# FG_with_AD9833.net
KiCad netlist of a schematic drawn in EAGLE
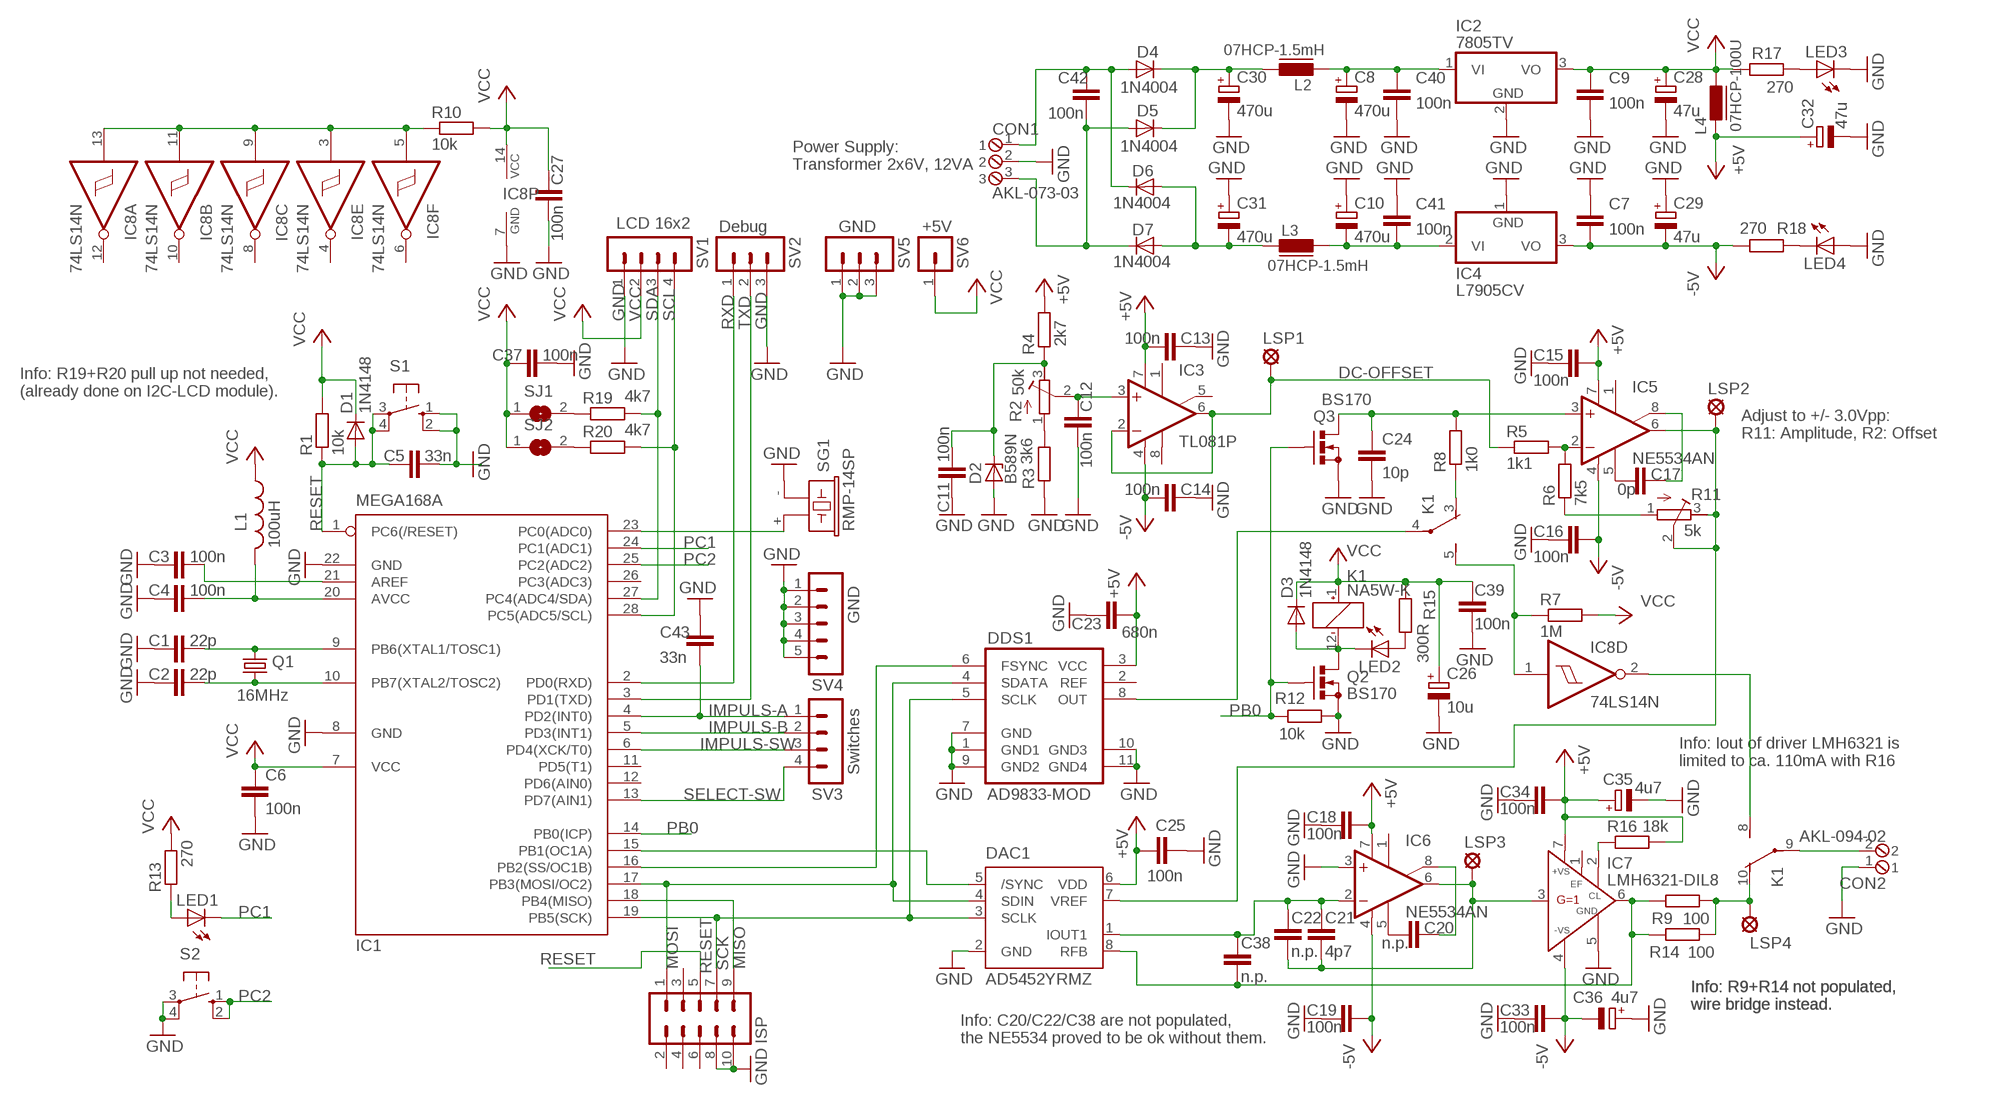
[diagram p0: schematic, sheet 1]

(export (version "E")
  (design (tool "Eeschema 10.0.6"))
  (components
    (comp (ref "C1")
      (value "22p")
      (footprint "eagle-import:C025-024X044")
      (libsource (lib "eagle-import") (part "C-EU025-024X044"))
    )
    (comp (ref "C2")
      (value "22p")
      (footprint "eagle-import:C025-024X044")
      (libsource (lib "eagle-import") (part "C-EU025-024X044"))
    )
    (comp (ref "C3")
      (value "100n")
      (footprint "eagle-import:C050-024X044")
      (libsource (lib "eagle-import") (part "C-EU050-024X044"))
    )
    (comp (ref "C4")
      (value "100n")
      (footprint "eagle-import:C050-024X044")
      (libsource (lib "eagle-import") (part "C-EU050-024X044"))
    )
    (comp (ref "C5")
      (value "33n")
      (footprint "eagle-import:C025-024X044")
      (libsource (lib "eagle-import") (part "C-EU025-024X044"))
    )
    (comp (ref "C6")
      (value "100n")
      (footprint "eagle-import:C050-024X044")
      (libsource (lib "eagle-import") (part "C-EU050-024X044"))
    )
    (comp (ref "C7")
      (value "100n")
      (footprint "eagle-import:C050-024X044")
      (libsource (lib "eagle-import") (part "C-EU050-024X044"))
    )
    (comp (ref "C8")
      (value "470u")
      (footprint "eagle-import:E3,5-8")
      (libsource (lib "eagle-import") (part "CPOL-EUE3.5-8"))
    )
    (comp (ref "C9")
      (value "100n")
      (footprint "eagle-import:C050-024X044")
      (libsource (lib "eagle-import") (part "C-EU050-024X044"))
    )
    (comp (ref "C10")
      (value "470u")
      (footprint "eagle-import:E3,5-8")
      (libsource (lib "eagle-import") (part "CPOL-EUE3.5-8"))
    )
    (comp (ref "C11")
      (value "100n")
      (footprint "eagle-import:C050-024X044")
      (libsource (lib "eagle-import") (part "C-EU050-024X044"))
    )
    (comp (ref "C12")
      (value "100n")
      (footprint "eagle-import:C050-024X044")
      (libsource (lib "eagle-import") (part "C-EU050-024X044"))
    )
    (comp (ref "C13")
      (value "100n")
      (footprint "eagle-import:C050-024X044")
      (libsource (lib "eagle-import") (part "C-EU050-024X044"))
    )
    (comp (ref "C14")
      (value "100n")
      (footprint "eagle-import:C050-024X044")
      (libsource (lib "eagle-import") (part "C-EU050-024X044"))
    )
    (comp (ref "C15")
      (value "100n")
      (footprint "eagle-import:C050-024X044")
      (libsource (lib "eagle-import") (part "C-EU050-024X044"))
    )
    (comp (ref "C16")
      (value "100n")
      (footprint "eagle-import:C050-024X044")
      (libsource (lib "eagle-import") (part "C-EU050-024X044"))
    )
    (comp (ref "C17")
      (value "0p")
      (footprint "eagle-import:C025-024X044")
      (libsource (lib "eagle-import") (part "C-EU025-024X044"))
    )
    (comp (ref "C18")
      (value "100n")
      (footprint "eagle-import:C050-024X044")
      (libsource (lib "eagle-import") (part "C-EU050-024X044"))
    )
    (comp (ref "C19")
      (value "100n")
      (footprint "eagle-import:C050-024X044")
      (libsource (lib "eagle-import") (part "C-EU050-024X044"))
    )
    (comp (ref "C20")
      (value "n.p.")
      (footprint "eagle-import:C025-024X044")
      (libsource (lib "eagle-import") (part "C-EU025-024X044"))
    )
    (comp (ref "C21")
      (value "4p7")
      (footprint "eagle-import:C025-024X044")
      (libsource (lib "eagle-import") (part "C-EU025-024X044"))
    )
    (comp (ref "C22")
      (value "n.p.")
      (footprint "eagle-import:C025-024X044")
      (libsource (lib "eagle-import") (part "C-EU025-024X044"))
    )
    (comp (ref "C23")
      (value "680n")
      (footprint "eagle-import:C050-024X044")
      (libsource (lib "eagle-import") (part "C-EU050-024X044"))
    )
    (comp (ref "C24")
      (value "10p")
      (footprint "eagle-import:C025-024X044")
      (libsource (lib "eagle-import") (part "C-EU025-024X044"))
    )
    (comp (ref "C25")
      (value "100n")
      (footprint "eagle-import:C050-024X044")
      (libsource (lib "eagle-import") (part "C-EU050-024X044"))
    )
    (comp (ref "C26")
      (value "10u")
      (footprint "eagle-import:TT2D4")
      (libsource (lib "eagle-import") (part "CPOL-EUTT2D4"))
    )
    (comp (ref "C27")
      (value "100n")
      (footprint "eagle-import:C050-024X044")
      (libsource (lib "eagle-import") (part "C-EU050-024X044"))
    )
    (comp (ref "C28")
      (value "47u")
      (footprint "eagle-import:E2,5-6")
      (libsource (lib "eagle-import") (part "CPOL-EUE2.5-6"))
    )
    (comp (ref "C29")
      (value "47u")
      (footprint "eagle-import:E2,5-6")
      (libsource (lib "eagle-import") (part "CPOL-EUE2.5-6"))
    )
    (comp (ref "C30")
      (value "470u")
      (footprint "eagle-import:E3,5-8")
      (libsource (lib "eagle-import") (part "CPOL-EUE3.5-8"))
    )
    (comp (ref "C31")
      (value "470u")
      (footprint "eagle-import:E3,5-8")
      (libsource (lib "eagle-import") (part "CPOL-EUE3.5-8"))
    )
    (comp (ref "C32")
      (value "47u")
      (footprint "eagle-import:E2,5-6")
      (libsource (lib "eagle-import") (part "CPOL-EUE2.5-6"))
    )
    (comp (ref "C33")
      (value "100n")
      (footprint "eagle-import:C050-024X044")
      (libsource (lib "eagle-import") (part "C-EU050-024X044"))
    )
    (comp (ref "C34")
      (value "100n")
      (footprint "eagle-import:C050-024X044")
      (libsource (lib "eagle-import") (part "C-EU050-024X044"))
    )
    (comp (ref "C35")
      (value "4u7")
      (footprint "eagle-import:TT2D4")
      (libsource (lib "eagle-import") (part "CPOL-EUTT2D4"))
    )
    (comp (ref "C36")
      (value "4u7")
      (footprint "eagle-import:TT2D4")
      (libsource (lib "eagle-import") (part "CPOL-EUTT2D4"))
    )
    (comp (ref "C37")
      (value "100n")
      (footprint "eagle-import:C050-024X044")
      (libsource (lib "eagle-import") (part "C-EU050-024X044"))
    )
    (comp (ref "C38")
      (value "n.p.")
      (footprint "eagle-import:C025-024X044")
      (libsource (lib "eagle-import") (part "C-EU025-024X044"))
    )
    (comp (ref "C39")
      (value "100n")
      (footprint "eagle-import:C050-024X044")
      (libsource (lib "eagle-import") (part "C-EU050-024X044"))
    )
    (comp (ref "C40")
      (value "100n")
      (footprint "eagle-import:C050-024X044")
      (libsource (lib "eagle-import") (part "C-EU050-024X044"))
    )
    (comp (ref "C41")
      (value "100n")
      (footprint "eagle-import:C050-024X044")
      (libsource (lib "eagle-import") (part "C-EU050-024X044"))
    )
    (comp (ref "C42")
      (value "100n")
      (footprint "eagle-import:C050-024X044")
      (libsource (lib "eagle-import") (part "C-EU050-024X044"))
    )
    (comp (ref "C43")
      (value "33n")
      (footprint "eagle-import:C050-024X044")
      (libsource (lib "eagle-import") (part "C-EU050-024X044"))
    )
    (comp (ref "CON1")
      (value "AKL-073-03")
      (footprint "eagle-import:AKL-073-03")
      (libsource (lib "eagle-import") (part "AKL-073-03"))
    )
    (comp (ref "CON2")
      (value "AKL-094-02")
      (footprint "eagle-import:AKL-094-02")
      (libsource (lib "eagle-import") (part "AKL-094-02"))
    )
    (comp (ref "D1")
      (value "1N4148")
      (footprint "eagle-import:DO35-10")
      (libsource (lib "eagle-import") (part "1N4148DO35-10"))
    )
    (comp (ref "D2")
      (value "B589N")
      (footprint "eagle-import:TO-92H")
      (libsource (lib "eagle-import") (part "B589N"))
    )
    (comp (ref "D3")
      (value "1N4148")
      (footprint "eagle-import:DO35-7")
      (libsource (lib "eagle-import") (part "1N4148DO35-7"))
    )
    (comp (ref "D4")
      (value "1N4004")
      (footprint "eagle-import:DO41-10")
      (libsource (lib "eagle-import") (part "1N4004"))
    )
    (comp (ref "D5")
      (value "1N4004")
      (footprint "eagle-import:DO41-10")
      (libsource (lib "eagle-import") (part "1N4004"))
    )
    (comp (ref "D6")
      (value "1N4004")
      (footprint "eagle-import:DO41-10")
      (libsource (lib "eagle-import") (part "1N4004"))
    )
    (comp (ref "D7")
      (value "1N4004")
      (footprint "eagle-import:DO41-10")
      (libsource (lib "eagle-import") (part "1N4004"))
    )
    (comp (ref "DAC1")
      (value "AD5452YRMZ")
      (footprint "eagle-import:MSOP08")
      (libsource (lib "eagle-import") (part "AD5452YRMZ"))
    )
    (comp (ref "DDS1")
      (value "AD9833-MOD")
      (footprint "eagle-import:AD9833-MOD")
      (libsource (lib "eagle-import") (part "AD9833-MOD"))
    )
    (comp (ref "IC1")
      (value "MEGA168A")
      (footprint "eagle-import:DIL28-3")
      (libsource (lib "eagle-import") (part "MEGA8-P"))
    )
    (comp (ref "IC2")
      (value "7805TV")
      (footprint "eagle-import:TO220V")
      (libsource (lib "eagle-import") (part "78TV05"))
    )
    (comp (ref "IC3")
      (value "TL081P")
      (footprint "eagle-import:DIL08")
      (libsource (lib "eagle-import") (part "TL081P"))
    )
    (comp (ref "IC4")
      (value "L7905CV")
      (footprint "eagle-import:TO220-V")
      (libsource (lib "eagle-import") (part "L7905CV"))
    )
    (comp (ref "IC5")
      (value "NE5534AN")
      (footprint "eagle-import:DIL08")
      (libsource (lib "eagle-import") (part "NE5534NA"))
    )
    (comp (ref "IC6")
      (value "NE5534AN")
      (footprint "eagle-import:DIL08")
      (libsource (lib "eagle-import") (part "NE5534NA"))
    )
    (comp (ref "IC7")
      (value "LMH6321-DIL8")
      (footprint "eagle-import:DIL08-ADAP")
      (libsource (lib "eagle-import") (part "LMH6321-DIL8"))
    )
    (comp (ref "IC8")
      (value "74LS14N")
      (footprint "eagle-import:DIL14")
      (libsource (lib "eagle-import") (part "7414NLS"))
    )
    (comp (ref "ISP")
      (value "ML10")
      (footprint "eagle-import:ML10")
      (libsource (lib "eagle-import") (part "ML10"))
    )
    (comp (ref "K1")
      (value "NA5W-K")
      (footprint "eagle-import:HX")
      (libsource (lib "eagle-import") (part "NA5W-K"))
    )
    (comp (ref "L1")
      (value "100uH")
      (footprint "eagle-import:0207_10")
      (libsource (lib "eagle-import") (part "L-US0207/10"))
    )
    (comp (ref "L2")
      (value "07HCP-1.5mH")
      (footprint "eagle-import:FASTRON_07HCP_INDUCTOR")
      (libsource (lib "eagle-import") (part "07HCP-100U"))
    )
    (comp (ref "L3")
      (value "07HCP-1.5mH")
      (footprint "eagle-import:FASTRON_07HCP_INDUCTOR")
      (libsource (lib "eagle-import") (part "07HCP-100U"))
    )
    (comp (ref "L4")
      (value "07HCP-100U")
      (footprint "eagle-import:FASTRON_07HCP_INDUCTOR")
      (libsource (lib "eagle-import") (part "07HCP-100U"))
    )
    (comp (ref "LED1")
      (value "LED5MM")
      (footprint "eagle-import:LED5MM")
      (libsource (lib "eagle-import") (part "LED5MM"))
    )
    (comp (ref "LED2")
      (value "LED5MM")
      (footprint "eagle-import:LED5MM")
      (libsource (lib "eagle-import") (part "LED5MM"))
    )
    (comp (ref "LED3")
      (value "LED5MM")
      (footprint "eagle-import:LED5MM")
      (libsource (lib "eagle-import") (part "LED5MM"))
    )
    (comp (ref "LED4")
      (value "LED5MM")
      (footprint "eagle-import:LED5MM")
      (libsource (lib "eagle-import") (part "LED5MM"))
    )
    (comp (ref "LSP1")
      (value "LSP11")
      (footprint "eagle-import:LSP11")
      (libsource (lib "eagle-import") (part "LSP11"))
    )
    (comp (ref "LSP2")
      (value "LSP11")
      (footprint "eagle-import:LSP11")
      (libsource (lib "eagle-import") (part "LSP11"))
    )
    (comp (ref "LSP3")
      (value "LSP11")
      (footprint "eagle-import:LSP11")
      (libsource (lib "eagle-import") (part "LSP11"))
    )
    (comp (ref "LSP4")
      (value "LSP11")
      (footprint "eagle-import:LSP11")
      (libsource (lib "eagle-import") (part "LSP11"))
    )
    (comp (ref "Q1")
      (value "16MHz")
      (footprint "eagle-import:HC49_S")
      (libsource (lib "eagle-import") (part "CRYSTALHC49S"))
    )
    (comp (ref "Q2")
      (value "BS170")
      (footprint "eagle-import:SOT54E")
      (libsource (lib "eagle-import") (part "BS170"))
    )
    (comp (ref "Q3")
      (value "BS170")
      (footprint "eagle-import:SOT54E")
      (libsource (lib "eagle-import") (part "BS170"))
    )
    (comp (ref "R1")
      (value "10k")
      (footprint "eagle-import:0207_10")
      (libsource (lib "eagle-import") (part "R-EU_0207/10"))
    )
    (comp (ref "R2")
      (value "50k")
      (footprint "eagle-import:RTRIM64W")
      (libsource (lib "eagle-import") (part "R-TRIMM64W"))
    )
    (comp (ref "R3")
      (value "3k6")
      (footprint "eagle-import:0207_10")
      (libsource (lib "eagle-import") (part "R-EU_0207/10"))
    )
    (comp (ref "R4")
      (value "2k7")
      (footprint "eagle-import:0207_10")
      (libsource (lib "eagle-import") (part "R-EU_0207/10"))
    )
    (comp (ref "R5")
      (value "1k1")
      (footprint "eagle-import:0207_10")
      (libsource (lib "eagle-import") (part "R-EU_0207/10"))
    )
    (comp (ref "R6")
      (value "7k5")
      (footprint "eagle-import:0207_10")
      (libsource (lib "eagle-import") (part "R-EU_0207/10"))
    )
    (comp (ref "R7")
      (value "1M")
      (footprint "eagle-import:0207_10")
      (libsource (lib "eagle-import") (part "R-EU_0207/10"))
    )
    (comp (ref "R8")
      (value "1k0")
      (footprint "eagle-import:0207_10")
      (libsource (lib "eagle-import") (part "R-EU_0207/10"))
    )
    (comp (ref "R9")
      (value "100")
      (footprint "eagle-import:0207_10")
      (libsource (lib "eagle-import") (part "R-EU_0207/10"))
    )
    (comp (ref "R10")
      (value "10k")
      (footprint "eagle-import:0207_10")
      (libsource (lib "eagle-import") (part "R-EU_0207/10"))
    )
    (comp (ref "R11")
      (value "5k")
      (footprint "eagle-import:RTRIM64W")
      (libsource (lib "eagle-import") (part "R-TRIMM64W"))
    )
    (comp (ref "R12")
      (value "10k")
      (footprint "eagle-import:0207_10")
      (libsource (lib "eagle-import") (part "R-EU_0207/10"))
    )
    (comp (ref "R13")
      (value "270")
      (footprint "eagle-import:0207_10")
      (libsource (lib "eagle-import") (part "R-EU_0207/10"))
    )
    (comp (ref "R14")
      (value "100")
      (footprint "eagle-import:0207_10")
      (libsource (lib "eagle-import") (part "R-EU_0207/10"))
    )
    (comp (ref "R15")
      (value "300R")
      (footprint "eagle-import:0207_10")
      (libsource (lib "eagle-import") (part "R-EU_0207/10"))
    )
    (comp (ref "R16")
      (value "18k")
      (footprint "eagle-import:0207_10")
      (libsource (lib "eagle-import") (part "R-EU_0207/10"))
    )
    (comp (ref "R17")
      (value "270")
      (footprint "eagle-import:0207_10")
      (libsource (lib "eagle-import") (part "R-EU_0207/10"))
    )
    (comp (ref "R18")
      (value "270")
      (footprint "eagle-import:0207_10")
      (libsource (lib "eagle-import") (part "R-EU_0207/10"))
    )
    (comp (ref "R19")
      (value "4k7")
      (footprint "eagle-import:0207_10")
      (libsource (lib "eagle-import") (part "R-EU_0207/10"))
    )
    (comp (ref "R20")
      (value "4k7")
      (footprint "eagle-import:0207_10")
      (libsource (lib "eagle-import") (part "R-EU_0207/10"))
    )
    (comp (ref "S1")
      (value "10-XX")
      (footprint "eagle-import:B3F-10XX")
      (fields (field (name "MPN") "B3F-1000"))
      (libsource (lib "eagle-import") (part "10-XX"))
    )
    (comp (ref "S2")
      (value "10-XX")
      (footprint "eagle-import:B3F-10XX")
      (fields (field (name "MPN") "B3F-1000"))
      (libsource (lib "eagle-import") (part "10-XX"))
    )
    (comp (ref "SG1")
      (value "RMP-14SP")
      (footprint "eagle-import:F_CM12P")
      (libsource (lib "eagle-import") (part "F/CM12P"))
    )
    (comp (ref "SJ1") (value "SJ") (footprint "eagle-import:SJ") (libsource (lib "eagle-import") (part "SJ")))
    (comp (ref "SJ2") (value "SJ") (footprint "eagle-import:SJ") (libsource (lib "eagle-import") (part "SJ")))
    (comp (ref "SV1")
      (value "MA04-1")
      (footprint "eagle-import:MA04-1")
      (libsource (lib "eagle-import") (part "MA04-1"))
    )
    (comp (ref "SV2")
      (value "MA03-1")
      (footprint "eagle-import:MA03-1")
      (libsource (lib "eagle-import") (part "MA03-1"))
    )
    (comp (ref "SV3")
      (value "MA04-1")
      (footprint "eagle-import:MA04-1")
      (libsource (lib "eagle-import") (part "MA04-1"))
    )
    (comp (ref "SV4")
      (value "MA05-1")
      (footprint "eagle-import:MA05-1")
      (libsource (lib "eagle-import") (part "MA05-1"))
    )
    (comp (ref "SV5")
      (value "MA03-1")
      (footprint "eagle-import:MA03-1")
      (libsource (lib "eagle-import") (part "MA03-1"))
    )
    (comp (ref "SV6")
      (value "MA01-1")
      (footprint "eagle-import:MA01-1")
      (libsource (lib "eagle-import") (part "MA01-1"))
    )
  )
  (nets
    (net (code "1") (name "+5V") (class "Default")
      (node (ref "C13") (pin "2") (pinfunction "2_2") (pintype "passive"))
      (node (ref "C15") (pin "2") (pinfunction "2_2") (pintype "passive"))
      (node (ref "C18") (pin "2") (pinfunction "2_2") (pintype "passive"))
      (node (ref "C23") (pin "2") (pinfunction "2_2") (pintype "passive"))
      (node (ref "C25") (pin "1") (pinfunction "1_1") (pintype "passive"))
      (node (ref "C32") (pin "+") (pinfunction "+_+") (pintype "passive"))
      (node (ref "C34") (pin "2") (pinfunction "2_2") (pintype "passive"))
      (node (ref "C35") (pin "+") (pinfunction "+_+") (pintype "passive"))
      (node (ref "DAC1") (pin "6") (pinfunction "VDD_6") (pintype "power_in"))
      (node (ref "DDS1") (pin "3") (pinfunction "VCC_3") (pintype "power_in"))
      (node (ref "IC3") (pin "7") (pinfunction "V+_7") (pintype "power_in"))
      (node (ref "IC5") (pin "7") (pinfunction "V+_7") (pintype "power_in"))
      (node (ref "IC6") (pin "7") (pinfunction "V+_7") (pintype "power_in"))
      (node (ref "IC7") (pin "7") (pinfunction "+VS_7") (pintype "power_in"))
      (node (ref "L4") (pin "1") (pinfunction "1_1") (pintype "passive"))
      (node (ref "R16") (pin "2") (pinfunction "2_2") (pintype "passive"))
      (node (ref "R4") (pin "2") (pinfunction "2_2") (pintype "passive"))
    )
    (net (code "2") (name "-5V") (class "Default")
      (node (ref "C14") (pin "2") (pinfunction "2_2") (pintype "passive"))
      (node (ref "C16") (pin "2") (pinfunction "2_2") (pintype "passive"))
      (node (ref "C19") (pin "2") (pinfunction "2_2") (pintype "passive"))
      (node (ref "C29") (pin "-") (pinfunction "-_-") (pintype "passive"))
      (node (ref "C33") (pin "2") (pinfunction "2_2") (pintype "passive"))
      (node (ref "C36") (pin "-") (pinfunction "-_-") (pintype "passive"))
      (node (ref "C7") (pin "2") (pinfunction "2_2") (pintype "passive"))
      (node (ref "IC3") (pin "4") (pinfunction "V-_4") (pintype "power_in"))
      (node (ref "IC4") (pin "3") (pinfunction "VO_3") (pintype "passive"))
      (node (ref "IC5") (pin "4") (pinfunction "V-_4") (pintype "power_in"))
      (node (ref "IC6") (pin "4") (pinfunction "V-_4") (pintype "power_in"))
      (node (ref "IC7") (pin "4") (pinfunction "-VS_4") (pintype "power_in"))
      (node (ref "R18") (pin "1") (pinfunction "1_1") (pintype "passive"))
    )
    (net (code "3") (name "/DC-OFFSET") (class "Default")
      (node (ref "IC3") (pin "2") (pinfunction "-IN_2") (pintype "input"))
      (node (ref "IC3") (pin "6") (pinfunction "OUT_6") (pintype "output"))
      (node (ref "LSP1") (pin "MP") (pinfunction "MP_MP") (pintype "passive"))
      (node (ref "R5") (pin "1") (pinfunction "1_1") (pintype "passive"))
    )
    (net (code "4") (name "/IMPULS-A") (class "Default")
      (node (ref "C43") (pin "2") (pinfunction "2_2") (pintype "passive"))
      (node (ref "IC1") (pin "4") (pinfunction "PD2(INT0)_4") (pintype "bidirectional"))
      (node (ref "SV3") (pin "1") (pinfunction "1_1") (pintype "passive"))
    )
    (net (code "5") (name "/IMPULS-B") (class "Default")
      (node (ref "IC1") (pin "5") (pinfunction "PD3(INT1)_5") (pintype "bidirectional"))
      (node (ref "SV3") (pin "2") (pinfunction "2_2") (pintype "passive"))
    )
    (net (code "6") (name "/IMPULS-SW") (class "Default")
      (node (ref "IC1") (pin "6") (pinfunction "PD4(XCK/T0)_6") (pintype "bidirectional"))
      (node (ref "SV3") (pin "3") (pinfunction "3_3") (pintype "passive"))
    )
    (net (code "7") (name "/MISO") (class "Default")
      (node (ref "IC1") (pin "18") (pinfunction "PB4(MISO)_18") (pintype "bidirectional"))
      (node (ref "ISP") (pin "9") (pinfunction "9_9") (pintype "passive"))
    )
    (net (code "8") (name "/MOSI") (class "Default")
      (node (ref "DAC1") (pin "4") (pinfunction "SDIN_4") (pintype "input"))
      (node (ref "DDS1") (pin "4") (pinfunction "SDATA_4") (pintype "input"))
      (node (ref "IC1") (pin "17") (pinfunction "PB3(MOSI/OC2)_17") (pintype "bidirectional"))
      (node (ref "ISP") (pin "1") (pinfunction "1_1") (pintype "passive"))
    )
    (net (code "9") (name "/PB0") (class "Default")
      (node (ref "IC1") (pin "14") (pinfunction "PB0(ICP)_14") (pintype "bidirectional"))
      (node (ref "Q2") (pin "G") (pinfunction "G_G") (pintype "passive"))
      (node (ref "Q3") (pin "G") (pinfunction "G_G") (pintype "passive"))
      (node (ref "R12") (pin "2") (pinfunction "2_2") (pintype "passive"))
    )
    (net (code "10") (name "/PC1") (class "Default")
      (node (ref "IC1") (pin "24") (pinfunction "PC1(ADC1)_24") (pintype "bidirectional"))
      (node (ref "LED1") (pin "K") (pinfunction "C_K") (pintype "passive"))
    )
    (net (code "11") (name "/PC2") (class "Default")
      (node (ref "IC1") (pin "25") (pinfunction "PC2(ADC2)_25") (pintype "bidirectional"))
      (node (ref "S2") (pin "1") (pinfunction "S_1") (pintype "passive"))
      (node (ref "S2") (pin "2") (pinfunction "S1_2") (pintype "passive"))
    )
    (net (code "12") (name "/RESET") (class "Default")
      (node (ref "C5") (pin "1") (pinfunction "1_1") (pintype "passive"))
      (node (ref "D1") (pin "A") (pinfunction "A_A") (pintype "passive"))
      (node (ref "IC1") (pin "1") (pinfunction "PC6(/RESET)_1") (pintype "bidirectional"))
      (node (ref "ISP") (pin "5") (pinfunction "5_5") (pintype "passive"))
      (node (ref "R1") (pin "1") (pinfunction "1_1") (pintype "passive"))
      (node (ref "S1") (pin "3") (pinfunction "P_3") (pintype "passive"))
      (node (ref "S1") (pin "4") (pinfunction "P1_4") (pintype "passive"))
    )
    (net (code "13") (name "/RXD") (class "Default")
      (node (ref "IC1") (pin "2") (pinfunction "PD0(RXD)_2") (pintype "bidirectional"))
      (node (ref "SV2") (pin "1") (pinfunction "1_1") (pintype "passive"))
    )
    (net (code "14") (name "/SCK") (class "Default")
      (node (ref "DAC1") (pin "3") (pinfunction "SCLK_3") (pintype "input"))
      (node (ref "DDS1") (pin "5") (pinfunction "SCLK_5") (pintype "input"))
      (node (ref "IC1") (pin "19") (pinfunction "PB5(SCK)_19") (pintype "bidirectional"))
      (node (ref "ISP") (pin "7") (pinfunction "7_7") (pintype "passive"))
    )
    (net (code "15") (name "/SCL") (class "Default")
      (node (ref "IC1") (pin "28") (pinfunction "PC5(ADC5/SCL)_28") (pintype "bidirectional"))
      (node (ref "R20") (pin "2") (pinfunction "2_2") (pintype "passive"))
      (node (ref "SV1") (pin "4") (pinfunction "4_4") (pintype "passive"))
    )
    (net (code "16") (name "/SDA") (class "Default")
      (node (ref "IC1") (pin "27") (pinfunction "PC4(ADC4/SDA)_27") (pintype "bidirectional"))
      (node (ref "R19") (pin "2") (pinfunction "2_2") (pintype "passive"))
      (node (ref "SV1") (pin "3") (pinfunction "3_3") (pintype "passive"))
    )
    (net (code "17") (name "/SELECT-SW") (class "Default")
      (node (ref "IC1") (pin "13") (pinfunction "PD7(AIN1)_13") (pintype "bidirectional"))
      (node (ref "SV3") (pin "4") (pinfunction "4_4") (pintype "passive"))
    )
    (net (code "18") (name "/TXD") (class "Default")
      (node (ref "IC1") (pin "3") (pinfunction "PD1(TXD)_3") (pintype "bidirectional"))
      (node (ref "SV2") (pin "2") (pinfunction "2_2") (pintype "passive"))
    )
    (net (code "19") (name "GND") (class "Default")
      (node (ref "C1") (pin "1") (pinfunction "1_1") (pintype "passive"))
      (node (ref "C10") (pin "+") (pinfunction "+_+") (pintype "passive"))
      (node (ref "C11") (pin "1") (pinfunction "1_1") (pintype "passive"))
      (node (ref "C12") (pin "2") (pinfunction "2_2") (pintype "passive"))
      (node (ref "C13") (pin "1") (pinfunction "1_1") (pintype "passive"))
      (node (ref "C14") (pin "1") (pinfunction "1_1") (pintype "passive"))
      (node (ref "C15") (pin "1") (pinfunction "1_1") (pintype "passive"))
      (node (ref "C16") (pin "1") (pinfunction "1_1") (pintype "passive"))
      (node (ref "C18") (pin "1") (pinfunction "1_1") (pintype "passive"))
      (node (ref "C19") (pin "1") (pinfunction "1_1") (pintype "passive"))
      (node (ref "C2") (pin "1") (pinfunction "1_1") (pintype "passive"))
      (node (ref "C23") (pin "1") (pinfunction "1_1") (pintype "passive"))
      (node (ref "C24") (pin "2") (pinfunction "2_2") (pintype "passive"))
      (node (ref "C25") (pin "2") (pinfunction "2_2") (pintype "passive"))
      (node (ref "C26") (pin "-") (pinfunction "-_-") (pintype "passive"))
      (node (ref "C27") (pin "2") (pinfunction "2_2") (pintype "passive"))
      (node (ref "C28") (pin "-") (pinfunction "-_-") (pintype "passive"))
      (node (ref "C29") (pin "+") (pinfunction "+_+") (pintype "passive"))
      (node (ref "C3") (pin "1") (pinfunction "1_1") (pintype "passive"))
      (node (ref "C30") (pin "-") (pinfunction "-_-") (pintype "passive"))
      (node (ref "C31") (pin "+") (pinfunction "+_+") (pintype "passive"))
      (node (ref "C32") (pin "-") (pinfunction "-_-") (pintype "passive"))
      (node (ref "C33") (pin "1") (pinfunction "1_1") (pintype "passive"))
      (node (ref "C34") (pin "1") (pinfunction "1_1") (pintype "passive"))
      (node (ref "C35") (pin "-") (pinfunction "-_-") (pintype "passive"))
      (node (ref "C36") (pin "+") (pinfunction "+_+") (pintype "passive"))
      (node (ref "C37") (pin "2") (pinfunction "2_2") (pintype "passive"))
      (node (ref "C39") (pin "1") (pinfunction "1_1") (pintype "passive"))
      (node (ref "C4") (pin "1") (pinfunction "1_1") (pintype "passive"))
      (node (ref "C40") (pin "2") (pinfunction "2_2") (pintype "passive"))
      (node (ref "C41") (pin "1") (pinfunction "1_1") (pintype "passive"))
      (node (ref "C43") (pin "1") (pinfunction "1_1") (pintype "passive"))
      (node (ref "C5") (pin "2") (pinfunction "2_2") (pintype "passive"))
      (node (ref "C6") (pin "2") (pinfunction "2_2") (pintype "passive"))
      (node (ref "C7") (pin "1") (pinfunction "1_1") (pintype "passive"))
      (node (ref "C8") (pin "-") (pinfunction "-_-") (pintype "passive"))
      (node (ref "C9") (pin "2") (pinfunction "2_2") (pintype "passive"))
      (node (ref "CON1") (pin "2") (pinfunction "2_2") (pintype "passive"))
      (node (ref "CON2") (pin "1") (pinfunction "1_1") (pintype "passive"))
      (node (ref "D2") (pin "2") (pinfunction "A_2") (pintype "passive"))
      (node (ref "DAC1") (pin "2") (pinfunction "GND_2") (pintype "power_in"))
      (node (ref "DDS1") (pin "1") (pinfunction "GND1_1") (pintype "power_in"))
      (node (ref "DDS1") (pin "10") (pinfunction "GND3_10") (pintype "power_in"))
      (node (ref "DDS1") (pin "11") (pinfunction "GND4_11") (pintype "power_in"))
      (node (ref "DDS1") (pin "7") (pinfunction "GND_7") (pintype "power_in"))
      (node (ref "DDS1") (pin "9") (pinfunction "GND2_9") (pintype "power_in"))
      (node (ref "IC1") (pin "22") (pinfunction "GND_22") (pintype "power_in"))
      (node (ref "IC1") (pin "8") (pinfunction "GND_8") (pintype "power_in"))
      (node (ref "IC2") (pin "2") (pinfunction "GND_2") (pintype "passive"))
      (node (ref "IC4") (pin "1") (pinfunction "GND_1") (pintype "passive"))
      (node (ref "IC6") (pin "3") (pinfunction "+IN_3") (pintype "input"))
      (node (ref "IC7") (pin "5") (pinfunction "GND_5") (pintype "passive"))
      (node (ref "IC8") (pin "7") (pinfunction "GND_7") (pintype "power_in"))
      (node (ref "ISP") (pin "10") (pinfunction "10_10") (pintype "passive"))
      (node (ref "ISP") (pin "8") (pinfunction "8_8") (pintype "passive"))
      (node (ref "LED3") (pin "K") (pinfunction "C_K") (pintype "passive"))
      (node (ref "LED4") (pin "A") (pinfunction "A_A") (pintype "passive"))
      (node (ref "Q2") (pin "S") (pinfunction "S_S") (pintype "passive"))
      (node (ref "Q3") (pin "S") (pinfunction "S_S") (pintype "passive"))
      (node (ref "R12") (pin "1") (pinfunction "1_1") (pintype "passive"))
      (node (ref "R3") (pin "1") (pinfunction "1_1") (pintype "passive"))
      (node (ref "S1") (pin "1") (pinfunction "S_1") (pintype "passive"))
      (node (ref "S1") (pin "2") (pinfunction "S1_2") (pintype "passive"))
      (node (ref "S2") (pin "3") (pinfunction "P_3") (pintype "passive"))
      (node (ref "S2") (pin "4") (pinfunction "P1_4") (pintype "passive"))
      (node (ref "SG1") (pin "-") (pinfunction "2_-") (pintype "passive"))
      (node (ref "SV1") (pin "1") (pinfunction "1_1") (pintype "passive"))
      (node (ref "SV2") (pin "3") (pinfunction "3_3") (pintype "passive"))
      (node (ref "SV4") (pin "1") (pinfunction "1_1") (pintype "passive"))
      (node (ref "SV4") (pin "2") (pinfunction "2_2") (pintype "passive"))
      (node (ref "SV4") (pin "3") (pinfunction "3_3") (pintype "passive"))
      (node (ref "SV4") (pin "4") (pinfunction "4_4") (pintype "passive"))
      (node (ref "SV4") (pin "5") (pinfunction "5_5") (pintype "passive"))
      (node (ref "SV5") (pin "1") (pinfunction "1_1") (pintype "passive"))
      (node (ref "SV5") (pin "2") (pinfunction "2_2") (pintype "passive"))
      (node (ref "SV5") (pin "3") (pinfunction "3_3") (pintype "passive"))
    )
    (net (code "20") (name "Net-(C30-Pad+)") (class "Default")
      (node (ref "C30") (pin "+") (pinfunction "+_+") (pintype "passive"))
      (node (ref "D4") (pin "C") (pinfunction "C_C") (pintype "passive"))
      (node (ref "D5") (pin "C") (pinfunction "C_C") (pintype "passive"))
      (node (ref "L2") (pin "2") (pinfunction "2_2") (pintype "passive"))
    )
    (net (code "21") (name "Net-(C31-Pad-)") (class "Default")
      (node (ref "C31") (pin "-") (pinfunction "-_-") (pintype "passive"))
      (node (ref "D6") (pin "A") (pinfunction "A_A") (pintype "passive"))
      (node (ref "D7") (pin "A") (pinfunction "A_A") (pintype "passive"))
      (node (ref "L3") (pin "1") (pinfunction "1_1") (pintype "passive"))
    )
    (net (code "22") (name "Net-(C42-Pad1)") (class "Default")
      (node (ref "C42") (pin "1") (pinfunction "1_1") (pintype "passive"))
      (node (ref "CON1") (pin "1") (pinfunction "1_1") (pintype "passive"))
      (node (ref "D4") (pin "A") (pinfunction "A_A") (pintype "passive"))
      (node (ref "D6") (pin "C") (pinfunction "C_C") (pintype "passive"))
    )
    (net (code "23") (name "Net-(C42-Pad2)") (class "Default")
      (node (ref "C42") (pin "2") (pinfunction "2_2") (pintype "passive"))
      (node (ref "CON1") (pin "3") (pinfunction "3_3") (pintype "passive"))
      (node (ref "D5") (pin "A") (pinfunction "A_A") (pintype "passive"))
      (node (ref "D7") (pin "C") (pinfunction "C_C") (pintype "passive"))
    )
    (net (code "24") (name "Net-(D2-C)") (class "Default")
      (node (ref "C11") (pin "2") (pinfunction "2_2") (pintype "passive"))
      (node (ref "D2") (pin "1") (pinfunction "C_1") (pintype "passive"))
      (node (ref "R2") (pin "3") (pinfunction "E_3") (pintype "passive"))
      (node (ref "R4") (pin "1") (pinfunction "1_1") (pintype "passive"))
    )
    (net (code "25") (name "Net-(DAC1-IOUT1)") (class "Default")
      (node (ref "C21") (pin "1") (pinfunction "1_1") (pintype "passive"))
      (node (ref "C22") (pin "1") (pinfunction "1_1") (pintype "passive"))
      (node (ref "C38") (pin "1") (pinfunction "1_1") (pintype "passive"))
      (node (ref "DAC1") (pin "1") (pinfunction "IOUT1_1") (pintype "output"))
      (node (ref "IC6") (pin "2") (pinfunction "-IN_2") (pintype "input"))
    )
    (net (code "26") (name "Net-(DAC1-RFB)") (class "Default")
      (node (ref "C38") (pin "2") (pinfunction "2_2") (pintype "passive"))
      (node (ref "DAC1") (pin "8") (pinfunction "RFB_8") (pintype "passive"))
      (node (ref "IC7") (pin "6") (pinfunction "OUT_6") (pintype "output"))
      (node (ref "R14") (pin "2") (pinfunction "2_2") (pintype "passive"))
      (node (ref "R9") (pin "2") (pinfunction "2_2") (pintype "passive"))
    )
    (net (code "27") (name "Net-(DAC1-VREF)") (class "Default")
      (node (ref "DAC1") (pin "7") (pinfunction "VREF_7") (pintype "power_in"))
      (node (ref "IC5") (pin "6") (pinfunction "OUT_6") (pintype "output"))
      (node (ref "LSP2") (pin "MP") (pinfunction "MP_MP") (pintype "passive"))
      (node (ref "R11") (pin "2") (pinfunction "S_2") (pintype "passive"))
      (node (ref "R11") (pin "3") (pinfunction "E_3") (pintype "passive"))
    )
    (net (code "28") (name "Net-(DAC1-{slash}SYNC)") (class "Default")
      (node (ref "DAC1") (pin "5") (pinfunction "/SYNC_5") (pintype "input"))
      (node (ref "IC1") (pin "15") (pinfunction "PB1(OC1A)_15") (pintype "bidirectional"))
    )
    (net (code "29") (name "Net-(DDS1-FSYNC)") (class "Default")
      (node (ref "DDS1") (pin "6") (pinfunction "FSYNC_6") (pintype "input"))
      (node (ref "IC1") (pin "16") (pinfunction "PB2(SS/OC1B)_16") (pintype "bidirectional"))
    )
    (net (code "30") (name "Net-(DDS1-OUT)") (class "Default")
      (node (ref "DDS1") (pin "8") (pinfunction "OUT_8") (pintype "output"))
      (node (ref "K1") (pin "4") (pinfunction "P_4") (pintype "passive"))
    )
    (net (code "31") (name "Net-(IC1-AREF)") (class "Default")
      (node (ref "C3") (pin "2") (pinfunction "2_2") (pintype "passive"))
      (node (ref "IC1") (pin "21") (pinfunction "AREF_21") (pintype "passive"))
    )
    (net (code "32") (name "Net-(IC1-AVCC)") (class "Default")
      (node (ref "C4") (pin "2") (pinfunction "2_2") (pintype "passive"))
      (node (ref "IC1") (pin "20") (pinfunction "AVCC_20") (pintype "power_in"))
      (node (ref "L1") (pin "2") (pinfunction "2_2") (pintype "passive"))
    )
    (net (code "33") (name "Net-(IC1-PB6(XTAL1{slash}TOSC1))") (class "Default")
      (node (ref "C1") (pin "2") (pinfunction "2_2") (pintype "passive"))
      (node (ref "IC1") (pin "9") (pinfunction "PB6(XTAL1/TOSC1)_9") (pintype "bidirectional"))
      (node (ref "Q1") (pin "2") (pinfunction "2_2") (pintype "passive"))
    )
    (net (code "34") (name "Net-(IC1-PB7(XTAL2{slash}TOSC2))") (class "Default")
      (node (ref "C2") (pin "2") (pinfunction "2_2") (pintype "passive"))
      (node (ref "IC1") (pin "10") (pinfunction "PB7(XTAL2/TOSC2)_10") (pintype "bidirectional"))
      (node (ref "Q1") (pin "1") (pinfunction "1_1") (pintype "passive"))
    )
    (net (code "35") (name "Net-(IC1-PC0(ADC0))") (class "Default")
      (node (ref "IC1") (pin "23") (pinfunction "PC0(ADC0)_23") (pintype "bidirectional"))
      (node (ref "SG1") (pin "+") (pinfunction "1_+") (pintype "passive"))
    )
    (net (code "36") (name "Net-(IC2-VI)") (class "Default")
      (node (ref "C40") (pin "1") (pinfunction "1_1") (pintype "passive"))
      (node (ref "C8") (pin "+") (pinfunction "+_+") (pintype "passive"))
      (node (ref "IC2") (pin "1") (pinfunction "VI_1") (pintype "input"))
      (node (ref "L2") (pin "1") (pinfunction "1_1") (pintype "passive"))
    )
    (net (code "37") (name "Net-(IC3-+IN)") (class "Default")
      (node (ref "C12") (pin "1") (pinfunction "1_1") (pintype "passive"))
      (node (ref "IC3") (pin "3") (pinfunction "+IN_3") (pintype "input"))
      (node (ref "R2") (pin "2") (pinfunction "S_2") (pintype "passive"))
    )
    (net (code "38") (name "Net-(IC4-VI)") (class "Default")
      (node (ref "C10") (pin "-") (pinfunction "-_-") (pintype "passive"))
      (node (ref "C41") (pin "2") (pinfunction "2_2") (pintype "passive"))
      (node (ref "IC4") (pin "2") (pinfunction "VI_2") (pintype "input"))
      (node (ref "L3") (pin "2") (pinfunction "2_2") (pintype "passive"))
    )
    (net (code "39") (name "Net-(IC5-+IN)") (class "Default")
      (node (ref "C24") (pin "1") (pinfunction "1_1") (pintype "passive"))
      (node (ref "IC5") (pin "3") (pinfunction "+IN_3") (pintype "input"))
      (node (ref "Q3") (pin "D") (pinfunction "D_D") (pintype "passive"))
      (node (ref "R8") (pin "2") (pinfunction "2_2") (pintype "passive"))
    )
    (net (code "40") (name "Net-(IC5--IN)") (class "Default")
      (node (ref "IC5") (pin "2") (pinfunction "-IN_2") (pintype "input"))
      (node (ref "R5") (pin "2") (pinfunction "2_2") (pintype "passive"))
      (node (ref "R6") (pin "2") (pinfunction "2_2") (pintype "passive"))
    )
    (net (code "41") (name "Net-(IC5-CMP)") (class "Default")
      (node (ref "C17") (pin "1") (pinfunction "1_1") (pintype "passive"))
      (node (ref "IC5") (pin "5") (pinfunction "CMP_5") (pintype "passive"))
    )
    (net (code "42") (name "Net-(IC5-ON{slash}CMP)") (class "Default")
      (node (ref "C17") (pin "2") (pinfunction "2_2") (pintype "passive"))
      (node (ref "IC5") (pin "8") (pinfunction "ON/CMP_8") (pintype "passive"))
    )
    (net (code "43") (name "Net-(IC6-CMP)") (class "Default")
      (node (ref "C20") (pin "1") (pinfunction "1_1") (pintype "passive"))
      (node (ref "IC6") (pin "5") (pinfunction "CMP_5") (pintype "passive"))
    )
    (net (code "44") (name "Net-(IC6-ON{slash}CMP)") (class "Default")
      (node (ref "C20") (pin "2") (pinfunction "2_2") (pintype "passive"))
      (node (ref "IC6") (pin "8") (pinfunction "ON/CMP_8") (pintype "passive"))
    )
    (net (code "45") (name "Net-(IC6-OUT)") (class "Default")
      (node (ref "C21") (pin "2") (pinfunction "2_2") (pintype "passive"))
      (node (ref "C22") (pin "2") (pinfunction "2_2") (pintype "passive"))
      (node (ref "IC6") (pin "6") (pinfunction "OUT_6") (pintype "output"))
      (node (ref "IC7") (pin "3") (pinfunction "IN_3") (pintype "input"))
      (node (ref "LSP3") (pin "MP") (pinfunction "MP_MP") (pintype "passive"))
    )
    (net (code "46") (name "Net-(IC7-CL)") (class "Default")
      (node (ref "IC7") (pin "2") (pinfunction "CL_2") (pintype "passive"))
      (node (ref "R16") (pin "1") (pinfunction "1_1") (pintype "passive"))
    )
    (net (code "47") (name "Net-(IC8A-I)") (class "Default")
      (node (ref "IC8") (pin "11") (pinfunction "I_11") (pintype "input"))
      (node (ref "IC8") (pin "13") (pinfunction "I_13") (pintype "input"))
      (node (ref "IC8") (pin "3") (pinfunction "I_3") (pintype "input"))
      (node (ref "IC8") (pin "5") (pinfunction "I_5") (pintype "input"))
      (node (ref "IC8") (pin "9") (pinfunction "I_9") (pintype "input"))
      (node (ref "R10") (pin "1") (pinfunction "1_1") (pintype "passive"))
    )
    (net (code "48") (name "Net-(IC8D-I)") (class "Default")
      (node (ref "IC8") (pin "1") (pinfunction "I_1") (pintype "input"))
      (node (ref "K1") (pin "5") (pinfunction "S_5") (pintype "passive"))
      (node (ref "R7") (pin "1") (pinfunction "1_1") (pintype "passive"))
    )
    (net (code "49") (name "Net-(IC8D-O)") (class "Default")
      (node (ref "IC8") (pin "2") (pinfunction "O_2") (pintype "output"))
      (node (ref "K1") (pin "8") (pinfunction "S_8") (pintype "passive"))
    )
    (net (code "50") (name "Net-(K1A--)") (class "Default")
      (node (ref "D3") (pin "A") (pinfunction "A_A") (pintype "passive"))
      (node (ref "K1") (pin "12") (pinfunction "-_12") (pintype "passive"))
      (node (ref "LED2") (pin "K") (pinfunction "C_K") (pintype "passive"))
      (node (ref "Q2") (pin "D") (pinfunction "D_D") (pintype "passive"))
    )
    (net (code "51") (name "Net-(K1B-O)") (class "Default")
      (node (ref "K1") (pin "3") (pinfunction "O_3") (pintype "passive"))
      (node (ref "R8") (pin "1") (pinfunction "1_1") (pintype "passive"))
    )
    (net (code "52") (name "Net-(K1C-O)") (class "Default")
      (node (ref "K1") (pin "10") (pinfunction "O_10") (pintype "passive"))
      (node (ref "LSP4") (pin "MP") (pinfunction "MP_MP") (pintype "passive"))
      (node (ref "R14") (pin "1") (pinfunction "1_1") (pintype "passive"))
      (node (ref "R9") (pin "1") (pinfunction "1_1") (pintype "passive"))
    )
    (net (code "53") (name "Net-(K1C-P)") (class "Default")
      (node (ref "CON2") (pin "2") (pinfunction "2_2") (pintype "passive"))
      (node (ref "K1") (pin "9") (pinfunction "P_9") (pintype "passive"))
    )
    (net (code "54") (name "Net-(LED1-PadA)") (class "Default")
      (node (ref "LED1") (pin "A") (pinfunction "A_A") (pintype "passive"))
      (node (ref "R13") (pin "1") (pinfunction "1_1") (pintype "passive"))
    )
    (net (code "55") (name "Net-(LED2-PadA)") (class "Default")
      (node (ref "LED2") (pin "A") (pinfunction "A_A") (pintype "passive"))
      (node (ref "R15") (pin "2") (pinfunction "2_2") (pintype "passive"))
    )
    (net (code "56") (name "Net-(LED3-PadA)") (class "Default")
      (node (ref "LED3") (pin "A") (pinfunction "A_A") (pintype "passive"))
      (node (ref "R17") (pin "1") (pinfunction "1_1") (pintype "passive"))
    )
    (net (code "57") (name "Net-(LED4-C)") (class "Default")
      (node (ref "LED4") (pin "K") (pinfunction "C_K") (pintype "passive"))
      (node (ref "R18") (pin "2") (pinfunction "2_2") (pintype "passive"))
    )
    (net (code "58") (name "Net-(R2-A)") (class "Default")
      (node (ref "R2") (pin "1") (pinfunction "A_1") (pintype "passive"))
      (node (ref "R3") (pin "2") (pinfunction "2_2") (pintype "passive"))
    )
    (net (code "59") (name "Net-(R11-A)") (class "Default")
      (node (ref "R11") (pin "1") (pinfunction "A_1") (pintype "passive"))
      (node (ref "R6") (pin "1") (pinfunction "1_1") (pintype "passive"))
    )
    (net (code "60") (name "Net-(R19-Pad1)") (class "Default")
      (node (ref "R19") (pin "1") (pinfunction "1_1") (pintype "passive"))
      (node (ref "SJ1") (pin "2") (pinfunction "2_2") (pintype "passive"))
    )
    (net (code "61") (name "Net-(R20-Pad1)") (class "Default")
      (node (ref "R20") (pin "1") (pinfunction "1_1") (pintype "passive"))
      (node (ref "SJ2") (pin "2") (pinfunction "2_2") (pintype "passive"))
    )
    (net (code "62") (name "VCC") (class "Default")
      (node (ref "C26") (pin "+") (pinfunction "+_+") (pintype "passive"))
      (node (ref "C27") (pin "1") (pinfunction "1_1") (pintype "passive"))
      (node (ref "C28") (pin "+") (pinfunction "+_+") (pintype "passive"))
      (node (ref "C37") (pin "1") (pinfunction "1_1") (pintype "passive"))
      (node (ref "C39") (pin "2") (pinfunction "2_2") (pintype "passive"))
      (node (ref "C6") (pin "1") (pinfunction "1_1") (pintype "passive"))
      (node (ref "C9") (pin "1") (pinfunction "1_1") (pintype "passive"))
      (node (ref "D1") (pin "C") (pinfunction "C_C") (pintype "passive"))
      (node (ref "D3") (pin "C") (pinfunction "C_C") (pintype "passive"))
      (node (ref "IC1") (pin "7") (pinfunction "VCC_7") (pintype "power_in"))
      (node (ref "IC2") (pin "3") (pinfunction "VO_3") (pintype "passive"))
      (node (ref "IC8") (pin "14") (pinfunction "VCC_14") (pintype "power_in"))
      (node (ref "K1") (pin "1") (pinfunction "+_1") (pintype "passive"))
      (node (ref "L1") (pin "1") (pinfunction "1_1") (pintype "passive"))
      (node (ref "L4") (pin "2") (pinfunction "2_2") (pintype "passive"))
      (node (ref "R1") (pin "2") (pinfunction "2_2") (pintype "passive"))
      (node (ref "R10") (pin "2") (pinfunction "2_2") (pintype "passive"))
      (node (ref "R13") (pin "2") (pinfunction "2_2") (pintype "passive"))
      (node (ref "R15") (pin "1") (pinfunction "1_1") (pintype "passive"))
      (node (ref "R17") (pin "2") (pinfunction "2_2") (pintype "passive"))
      (node (ref "R7") (pin "2") (pinfunction "2_2") (pintype "passive"))
      (node (ref "SJ1") (pin "1") (pinfunction "1_1") (pintype "passive"))
      (node (ref "SJ2") (pin "1") (pinfunction "1_1") (pintype "passive"))
      (node (ref "SV1") (pin "2") (pinfunction "2_2") (pintype "passive"))
      (node (ref "SV6") (pin "1") (pinfunction "1_1") (pintype "passive"))
    )
    (net (code "63") (name "unconnected-(DDS1-REF-Pad2)") (class "Default")
      (node (ref "DDS1") (pin "2") (pinfunction "REF_2") (pintype "output"))
    )
    (net (code "64") (name "unconnected-(IC1-PC3(ADC3)-Pad26)") (class "Default")
      (node (ref "IC1") (pin "26") (pinfunction "PC3(ADC3)_26") (pintype "bidirectional"))
    )
    (net (code "65") (name "unconnected-(IC1-PD5(T1)-Pad11)") (class "Default")
      (node (ref "IC1") (pin "11") (pinfunction "PD5(T1)_11") (pintype "bidirectional"))
    )
    (net (code "66") (name "unconnected-(IC1-PD6(AIN0)-Pad12)") (class "Default")
      (node (ref "IC1") (pin "12") (pinfunction "PD6(AIN0)_12") (pintype "bidirectional"))
    )
    (net (code "67") (name "unconnected-(IC3-ON1-Pad1)") (class "Default")
      (node (ref "IC3") (pin "1") (pinfunction "ON1_1") (pintype "passive"))
    )
    (net (code "68") (name "unconnected-(IC3-ON2-Pad5)") (class "Default")
      (node (ref "IC3") (pin "5") (pinfunction "ON2_5") (pintype "passive"))
    )
    (net (code "69") (name "unconnected-(IC3-OPT-Pad8)") (class "Default")
      (node (ref "IC3") (pin "8") (pinfunction "OPT_8") (pintype "passive"))
    )
    (net (code "70") (name "unconnected-(IC5-ON-Pad1)") (class "Default")
      (node (ref "IC5") (pin "1") (pinfunction "ON_1") (pintype "passive"))
    )
    (net (code "71") (name "unconnected-(IC6-ON-Pad1)") (class "Default")
      (node (ref "IC6") (pin "1") (pinfunction "ON_1") (pintype "passive"))
    )
    (net (code "72") (name "unconnected-(IC7-EF-Pad1)") (class "Default")
      (node (ref "IC7") (pin "1") (pinfunction "EF_1") (pintype "passive"))
    )
    (net (code "73") (name "unconnected-(IC8A-O-Pad12)") (class "Default")
      (node (ref "IC8") (pin "12") (pinfunction "O_12") (pintype "output"))
    )
    (net (code "74") (name "unconnected-(IC8B-O-Pad10)") (class "Default")
      (node (ref "IC8") (pin "10") (pinfunction "O_10") (pintype "output"))
    )
    (net (code "75") (name "unconnected-(IC8C-O-Pad8)") (class "Default")
      (node (ref "IC8") (pin "8") (pinfunction "O_8") (pintype "output"))
    )
    (net (code "76") (name "unconnected-(IC8E-O-Pad4)") (class "Default")
      (node (ref "IC8") (pin "4") (pinfunction "O_4") (pintype "output"))
    )
    (net (code "77") (name "unconnected-(IC8F-O-Pad6)") (class "Default")
      (node (ref "IC8") (pin "6") (pinfunction "O_6") (pintype "output"))
    )
    (net (code "78") (name "unconnected-(ISP-Pad2)") (class "Default")
      (node (ref "ISP") (pin "2") (pinfunction "2_2") (pintype "passive"))
    )
    (net (code "79") (name "unconnected-(ISP-Pad3)") (class "Default")
      (node (ref "ISP") (pin "3") (pinfunction "3_3") (pintype "passive"))
    )
    (net (code "80") (name "unconnected-(ISP-Pad4)") (class "Default")
      (node (ref "ISP") (pin "4") (pinfunction "4_4") (pintype "passive"))
    )
    (net (code "81") (name "unconnected-(ISP-Pad6)") (class "Default")
      (node (ref "ISP") (pin "6") (pinfunction "6_6") (pintype "passive"))
    )
  )
)
